# ParkingSensor.net
KiCad netlist of a schematic drawn in EAGLE
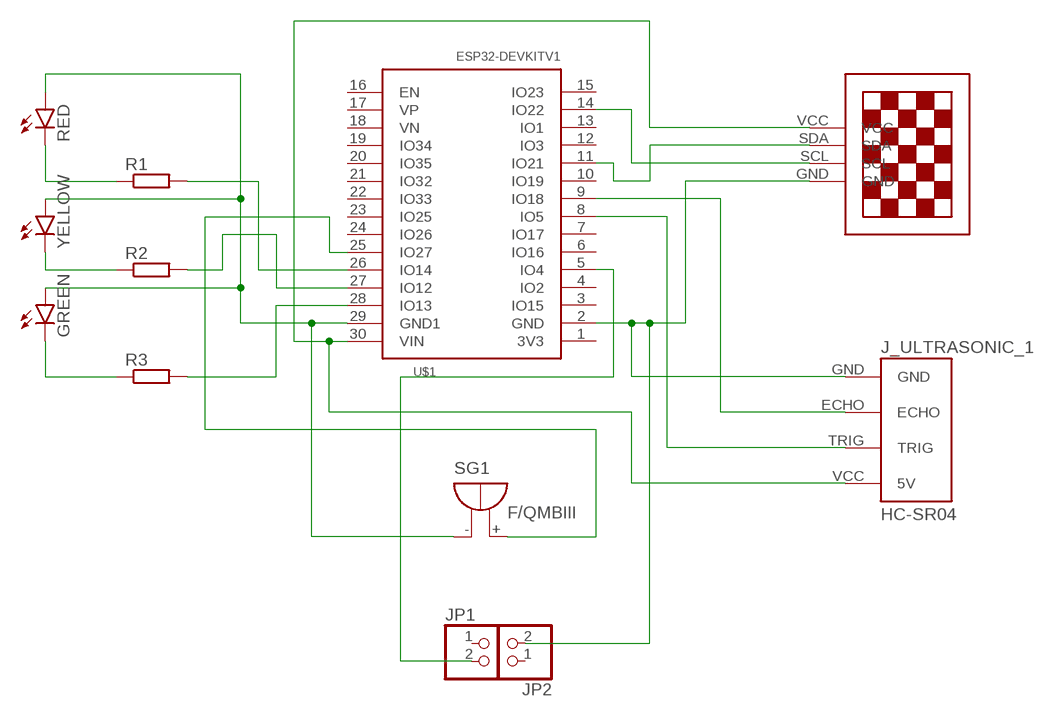
[diagram p0: schematic, sheet 1]

(export (version "E")
  (design (tool "Eeschema 10.0.6"))
  (components
    (comp (ref "GREEN")
      (value "LED5MM")
      (footprint "eagle-import:LED5MM")
      (libsource (lib "eagle-import") (part "LED5MM"))
    )
    (comp (ref "JP1")
      (value "PINHD-1X2")
      (footprint "eagle-import:1X02")
      (libsource (lib "eagle-import") (part "PINHD-1X2"))
    )
    (comp (ref "JP2")
      (value "PINHD-1X2")
      (footprint "eagle-import:1X02")
      (libsource (lib "eagle-import") (part "PINHD-1X2"))
    )
    (comp (ref "J_ULTRASONIC_1")
      (value "HC-SR04")
      (footprint "eagle-import:HC-SR04_FOOTPRINT")
      (libsource (lib "eagle-import") (part "HC-SR04"))
    )
    (comp (ref "R1")
      (value "R-EU_0204/7")
      (footprint "eagle-import:0204_7")
      (libsource (lib "eagle-import") (part "R-EU_0204/7"))
    )
    (comp (ref "R2")
      (value "R-EU_0204/7")
      (footprint "eagle-import:0204_7")
      (libsource (lib "eagle-import") (part "R-EU_0204/7"))
    )
    (comp (ref "R3")
      (value "R-EU_0204/7")
      (footprint "eagle-import:0204_7")
      (libsource (lib "eagle-import") (part "R-EU_0204/7"))
    )
    (comp (ref "RED")
      (value "LED5MM")
      (footprint "eagle-import:LED5MM")
      (libsource (lib "eagle-import") (part "LED5MM"))
    )
    (comp (ref "SG1")
      (value "F/QMBIII")
      (footprint "eagle-import:F_QMBIII")
      (libsource (lib "eagle-import") (part "F/QMBIII"))
    )
    (comp (ref "U$1")
      (value "ESP32DEVKITV1")
      (footprint "eagle-import:ESP32-DEVKITV1")
      (libsource (lib "eagle-import") (part "ESP32DEVKITV1"))
    )
    (comp (ref "U$3")
      (value "13\"OLED13\"OLED")
      (footprint "eagle-import:1.3_OLED")
      (libsource (lib "eagle-import") (part "13{dblquote}OLED13{dblquote}OLED"))
    )
    (comp (ref "YELLOW")
      (value "LED5MM")
      (footprint "eagle-import:LED5MM")
      (libsource (lib "eagle-import") (part "LED5MM"))
    )
  )
  (nets
    (net (code "1") (name "Net-(GREEN-C)") (class "Default")
      (node (ref "GREEN") (pin "K") (pinfunction "C_K") (pintype "passive"))
      (node (ref "R3") (pin "1") (pinfunction "1_1") (pintype "passive"))
    )
    (net (code "2") (name "Net-(J_ULTRASONIC_1-5V)") (class "Default")
      (node (ref "J_ULTRASONIC_1") (pin "VCC") (pinfunction "5V_VCC") (pintype "bidirectional"))
      (node (ref "U$1") (pin "30") (pinfunction "VIN_30") (pintype "bidirectional"))
      (node (ref "U$3") (pin "VCC") (pinfunction "VCC_VCC") (pintype "bidirectional"))
    )
    (net (code "3") (name "Net-(RED-C)") (class "Default")
      (node (ref "R1") (pin "1") (pinfunction "1_1") (pintype "passive"))
      (node (ref "RED") (pin "K") (pinfunction "C_K") (pintype "passive"))
    )
    (net (code "4") (name "Net-(SG1-+)") (class "Default")
      (node (ref "GREEN") (pin "A") (pinfunction "A_A") (pintype "passive"))
      (node (ref "RED") (pin "A") (pinfunction "A_A") (pintype "passive"))
      (node (ref "SG1") (pin "-") (pinfunction "+_-") (pintype "passive"))
      (node (ref "U$1") (pin "29") (pinfunction "GND1_29") (pintype "bidirectional"))
      (node (ref "YELLOW") (pin "A") (pinfunction "A_A") (pintype "passive"))
    )
    (net (code "5") (name "Net-(SG1--)") (class "Default")
      (node (ref "SG1") (pin "+") (pinfunction "-_+") (pintype "passive"))
      (node (ref "U$1") (pin "25") (pinfunction "IO27_25") (pintype "bidirectional"))
    )
    (net (code "6") (name "Net-(U$1-GND)") (class "Default")
      (node (ref "JP2") (pin "2") (pinfunction "2_2") (pintype "passive"))
      (node (ref "J_ULTRASONIC_1") (pin "GND") (pinfunction "GND_GND") (pintype "bidirectional"))
      (node (ref "U$1") (pin "2") (pinfunction "GND_2") (pintype "bidirectional"))
      (node (ref "U$3") (pin "GND") (pinfunction "GND_GND") (pintype "bidirectional"))
    )
    (net (code "7") (name "Net-(U$1-IO4)") (class "Default")
      (node (ref "JP1") (pin "2") (pinfunction "2_2") (pintype "passive"))
      (node (ref "U$1") (pin "5") (pinfunction "IO4_5") (pintype "bidirectional"))
    )
    (net (code "8") (name "Net-(U$1-IO5)") (class "Default")
      (node (ref "J_ULTRASONIC_1") (pin "TRIG") (pinfunction "TRIG_TRIG") (pintype "bidirectional"))
      (node (ref "U$1") (pin "8") (pinfunction "IO5_8") (pintype "bidirectional"))
    )
    (net (code "9") (name "Net-(U$1-IO12)") (class "Default")
      (node (ref "R2") (pin "2") (pinfunction "2_2") (pintype "passive"))
      (node (ref "U$1") (pin "27") (pinfunction "IO12_27") (pintype "bidirectional"))
    )
    (net (code "10") (name "Net-(U$1-IO13)") (class "Default")
      (node (ref "R3") (pin "2") (pinfunction "2_2") (pintype "passive"))
      (node (ref "U$1") (pin "28") (pinfunction "IO13_28") (pintype "bidirectional"))
    )
    (net (code "11") (name "Net-(U$1-IO14)") (class "Default")
      (node (ref "R1") (pin "2") (pinfunction "2_2") (pintype "passive"))
      (node (ref "U$1") (pin "26") (pinfunction "IO14_26") (pintype "bidirectional"))
    )
    (net (code "12") (name "Net-(U$1-IO18)") (class "Default")
      (node (ref "J_ULTRASONIC_1") (pin "ECHO") (pinfunction "ECHO_ECHO") (pintype "bidirectional"))
      (node (ref "U$1") (pin "9") (pinfunction "IO18_9") (pintype "bidirectional"))
    )
    (net (code "13") (name "Net-(U$1-IO21)") (class "Default")
      (node (ref "U$1") (pin "11") (pinfunction "IO21_11") (pintype "bidirectional"))
      (node (ref "U$3") (pin "SDA") (pinfunction "SDA_SDA") (pintype "bidirectional"))
    )
    (net (code "14") (name "Net-(U$1-IO22)") (class "Default")
      (node (ref "U$1") (pin "14") (pinfunction "IO22_14") (pintype "bidirectional"))
      (node (ref "U$3") (pin "SCL") (pinfunction "SCL_SCL") (pintype "bidirectional"))
    )
    (net (code "15") (name "Net-(YELLOW-C)") (class "Default")
      (node (ref "R2") (pin "1") (pinfunction "1_1") (pintype "passive"))
      (node (ref "YELLOW") (pin "K") (pinfunction "C_K") (pintype "passive"))
    )
    (net (code "16") (name "unconnected-(JP1-Pad1)") (class "Default")
      (node (ref "JP1") (pin "1") (pinfunction "1_1") (pintype "passive"))
    )
    (net (code "17") (name "unconnected-(JP2-Pad1)") (class "Default")
      (node (ref "JP2") (pin "1") (pinfunction "1_1") (pintype "passive"))
    )
    (net (code "18") (name "unconnected-(U$1-3V3-Pad1)") (class "Default")
      (node (ref "U$1") (pin "1") (pinfunction "3V3_1") (pintype "bidirectional"))
    )
    (net (code "19") (name "unconnected-(U$1-EN-Pad16)") (class "Default")
      (node (ref "U$1") (pin "16") (pinfunction "EN_16") (pintype "bidirectional"))
    )
    (net (code "20") (name "unconnected-(U$1-IO1-Pad13)") (class "Default")
      (node (ref "U$1") (pin "13") (pinfunction "IO1_13") (pintype "bidirectional"))
    )
    (net (code "21") (name "unconnected-(U$1-IO2-Pad4)") (class "Default")
      (node (ref "U$1") (pin "4") (pinfunction "IO2_4") (pintype "bidirectional"))
    )
    (net (code "22") (name "unconnected-(U$1-IO3-Pad12)") (class "Default")
      (node (ref "U$1") (pin "12") (pinfunction "IO3_12") (pintype "bidirectional"))
    )
    (net (code "23") (name "unconnected-(U$1-IO15-Pad3)") (class "Default")
      (node (ref "U$1") (pin "3") (pinfunction "IO15_3") (pintype "bidirectional"))
    )
    (net (code "24") (name "unconnected-(U$1-IO16-Pad6)") (class "Default")
      (node (ref "U$1") (pin "6") (pinfunction "IO16_6") (pintype "bidirectional"))
    )
    (net (code "25") (name "unconnected-(U$1-IO17-Pad7)") (class "Default")
      (node (ref "U$1") (pin "7") (pinfunction "IO17_7") (pintype "bidirectional"))
    )
    (net (code "26") (name "unconnected-(U$1-IO19-Pad10)") (class "Default")
      (node (ref "U$1") (pin "10") (pinfunction "IO19_10") (pintype "bidirectional"))
    )
    (net (code "27") (name "unconnected-(U$1-IO23-Pad15)") (class "Default")
      (node (ref "U$1") (pin "15") (pinfunction "IO23_15") (pintype "bidirectional"))
    )
    (net (code "28") (name "unconnected-(U$1-IO25-Pad23)") (class "Default")
      (node (ref "U$1") (pin "23") (pinfunction "IO25_23") (pintype "bidirectional"))
    )
    (net (code "29") (name "unconnected-(U$1-IO26-Pad24)") (class "Default")
      (node (ref "U$1") (pin "24") (pinfunction "IO26_24") (pintype "bidirectional"))
    )
    (net (code "30") (name "unconnected-(U$1-IO32-Pad21)") (class "Default")
      (node (ref "U$1") (pin "21") (pinfunction "IO32_21") (pintype "bidirectional"))
    )
    (net (code "31") (name "unconnected-(U$1-IO33-Pad22)") (class "Default")
      (node (ref "U$1") (pin "22") (pinfunction "IO33_22") (pintype "bidirectional"))
    )
    (net (code "32") (name "unconnected-(U$1-IO34-Pad19)") (class "Default")
      (node (ref "U$1") (pin "19") (pinfunction "IO34_19") (pintype "bidirectional"))
    )
    (net (code "33") (name "unconnected-(U$1-IO35-Pad20)") (class "Default")
      (node (ref "U$1") (pin "20") (pinfunction "IO35_20") (pintype "bidirectional"))
    )
    (net (code "34") (name "unconnected-(U$1-VN-Pad18)") (class "Default")
      (node (ref "U$1") (pin "18") (pinfunction "VN_18") (pintype "bidirectional"))
    )
    (net (code "35") (name "unconnected-(U$1-VP-Pad17)") (class "Default")
      (node (ref "U$1") (pin "17") (pinfunction "VP_17") (pintype "bidirectional"))
    )
  )
)
